# eeZeeISP.net
KiCad netlist of a schematic drawn in EAGLE
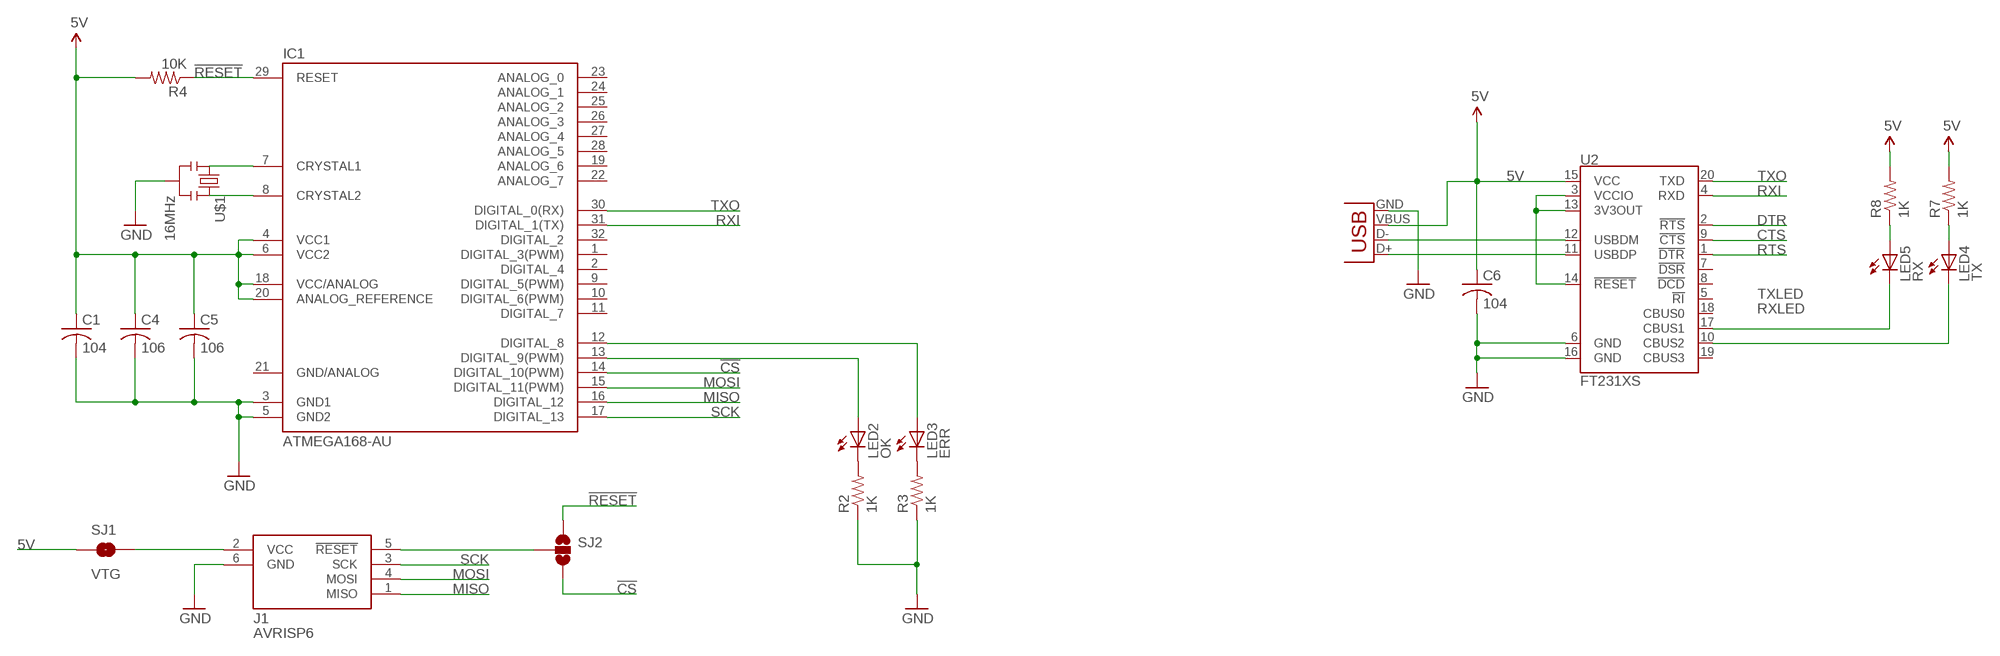
[diagram p0: schematic, sheet 1]

(export (version "E")
  (design (tool "Eeschema 10.0.6"))
  (components
    (comp (ref "C1")
      (value "104")
      (footprint "eagle-import:C0603")
      (libsource (lib "eagle-import") (part "C-USC0603"))
    )
    (comp (ref "C4")
      (value "106")
      (footprint "eagle-import:C0603")
      (libsource (lib "eagle-import") (part "C-USC0603"))
    )
    (comp (ref "C5")
      (value "106")
      (footprint "eagle-import:C0603")
      (libsource (lib "eagle-import") (part "C-USC0603"))
    )
    (comp (ref "C6")
      (value "104")
      (footprint "eagle-import:C0603")
      (libsource (lib "eagle-import") (part "C-USC0603"))
    )
    (comp (ref "IC1")
      (value "ATMEGA168-AU")
      (footprint "eagle-import:TQFP32-08")
      (libsource (lib "eagle-import") (part "ATMEGA168-AU"))
    )
    (comp (ref "J1")
      (value "AVRISP6")
      (footprint "eagle-import:CON6P2R")
      (libsource (lib "eagle-import") (part "AVRISP6"))
    )
    (comp (ref "LED2")
      (value "OK")
      (footprint "eagle-import:CHIPLED_1206")
      (libsource (lib "eagle-import") (part "LEDCHIPLED_1206"))
    )
    (comp (ref "LED3")
      (value "ERR")
      (footprint "eagle-import:CHIPLED_1206")
      (libsource (lib "eagle-import") (part "LEDCHIPLED_1206"))
    )
    (comp (ref "LED4")
      (value "TX")
      (footprint "eagle-import:CHIPLED_1206")
      (libsource (lib "eagle-import") (part "LEDCHIPLED_1206"))
    )
    (comp (ref "LED5")
      (value "RX")
      (footprint "eagle-import:CHIPLED_1206")
      (libsource (lib "eagle-import") (part "LEDCHIPLED_1206"))
    )
    (comp (ref "R2")
      (value "1K")
      (footprint "eagle-import:R0603")
      (libsource (lib "eagle-import") (part "R-US_R0603"))
    )
    (comp (ref "R3")
      (value "1K")
      (footprint "eagle-import:R0603")
      (libsource (lib "eagle-import") (part "R-US_R0603"))
    )
    (comp (ref "R4")
      (value "10K")
      (footprint "eagle-import:R0603")
      (libsource (lib "eagle-import") (part "R-US_R0603"))
    )
    (comp (ref "R7")
      (value "1K")
      (footprint "eagle-import:R0603")
      (libsource (lib "eagle-import") (part "R-US_R0603"))
    )
    (comp (ref "R8")
      (value "1K")
      (footprint "eagle-import:R0603")
      (libsource (lib "eagle-import") (part "R-US_R0603"))
    )
    (comp (ref "SJ1")
      (value "VTG")
      (footprint "eagle-import:SJ_2S-NO")
      (libsource (lib "eagle-import") (part "SOLDERJUMPERNO"))
    )
    (comp (ref "SJ2")
      (value "SOLDERJUMPER_2WAYS")
      (footprint "eagle-import:SJ_3")
      (libsource (lib "eagle-import") (part "SOLDERJUMPER_2WAYS"))
    )
    (comp (ref "U$1")
      (value "16MHz")
      (footprint "eagle-import:CSTCE_V_C")
      (libsource (lib "eagle-import") (part "RESONATOR_CSTCE_V_C"))
    )
    (comp (ref "U2")
      (value "FT231XS")
      (footprint "eagle-import:SSOP20_L")
      (libsource (lib "eagle-import") (part "FT231XS"))
    )
    (comp (ref "X2")
      (value "USB-SMD-NS")
      (footprint "eagle-import:USB-MINIB-NOSTOP")
      (libsource (lib "eagle-import") (part "USB-SMD-NS"))
    )
  )
  (nets
    (net (code "1") (name "/CTS") (class "Default")
      (node (ref "U2") (pin "9") (pinfunction "~{CTS}_9") (pintype "bidirectional"))
    )
    (net (code "2") (name "/DTR") (class "Default")
      (node (ref "U2") (pin "1") (pinfunction "~{DTR}_1") (pintype "bidirectional"))
    )
    (net (code "3") (name "/GND{slash}ANALOG") (class "Default")
      (node (ref "IC1") (pin "21") (pinfunction "GND/ANALOG_21") (pintype "power_in"))
    )
    (net (code "4") (name "/MISO") (class "Default")
      (node (ref "IC1") (pin "16") (pinfunction "DIGITAL_12_16") (pintype "bidirectional"))
      (node (ref "J1") (pin "1") (pinfunction "MISO_1") (pintype "input"))
    )
    (net (code "5") (name "/MOSI") (class "Default")
      (node (ref "IC1") (pin "15") (pinfunction "DIGITAL_11(PWM)_15") (pintype "bidirectional"))
      (node (ref "J1") (pin "4") (pinfunction "MOSI_4") (pintype "output"))
    )
    (net (code "6") (name "/RTS") (class "Default")
      (node (ref "U2") (pin "2") (pinfunction "~{RTS}_2") (pintype "bidirectional"))
    )
    (net (code "7") (name "/RXI") (class "Default")
      (node (ref "IC1") (pin "31") (pinfunction "DIGITAL_1(TX)_31") (pintype "bidirectional"))
      (node (ref "U2") (pin "4") (pinfunction "RXD_4") (pintype "bidirectional"))
    )
    (net (code "8") (name "/RXLED") (class "Default")
      (node (ref "LED5") (pin "C") (pinfunction "C_C") (pintype "passive"))
      (node (ref "U2") (pin "17") (pinfunction "CBUS1_17") (pintype "bidirectional"))
    )
    (net (code "9") (name "/SCK") (class "Default")
      (node (ref "IC1") (pin "17") (pinfunction "DIGITAL_13_17") (pintype "bidirectional"))
      (node (ref "J1") (pin "3") (pinfunction "SCK_3") (pintype "output"))
    )
    (net (code "10") (name "/TXLED") (class "Default")
      (node (ref "LED4") (pin "C") (pinfunction "C_C") (pintype "passive"))
      (node (ref "U2") (pin "10") (pinfunction "CBUS2_10") (pintype "bidirectional"))
    )
    (net (code "11") (name "/TXO") (class "Default")
      (node (ref "IC1") (pin "30") (pinfunction "DIGITAL_0(RX)_30") (pintype "bidirectional"))
      (node (ref "U2") (pin "20") (pinfunction "TXD_20") (pintype "bidirectional"))
    )
    (net (code "12") (name "/~{CS}") (class "Default")
      (node (ref "IC1") (pin "14") (pinfunction "DIGITAL_10(PWM)_14") (pintype "bidirectional"))
      (node (ref "SJ2") (pin "3") (pinfunction "3_3") (pintype "passive"))
    )
    (net (code "13") (name "/~{RESET}") (class "Default")
      (node (ref "IC1") (pin "29") (pinfunction "RESET_29") (pintype "bidirectional"))
      (node (ref "R4") (pin "1") (pinfunction "1_1") (pintype "passive"))
      (node (ref "SJ2") (pin "1") (pinfunction "1_1") (pintype "passive"))
    )
    (net (code "14") (name "5V") (class "Default")
      (node (ref "C1") (pin "1") (pinfunction "1_1") (pintype "passive"))
      (node (ref "C4") (pin "1") (pinfunction "1_1") (pintype "passive"))
      (node (ref "C5") (pin "1") (pinfunction "1_1") (pintype "passive"))
      (node (ref "C6") (pin "1") (pinfunction "1_1") (pintype "passive"))
      (node (ref "IC1") (pin "18") (pinfunction "VCC/ANALOG_18") (pintype "passive"))
      (node (ref "IC1") (pin "20") (pinfunction "ANALOG_REFERENCE_20") (pintype "passive"))
      (node (ref "IC1") (pin "4") (pinfunction "VCC1_4") (pintype "power_in"))
      (node (ref "IC1") (pin "6") (pinfunction "VCC2_6") (pintype "power_in"))
      (node (ref "R4") (pin "2") (pinfunction "2_2") (pintype "passive"))
      (node (ref "R7") (pin "2") (pinfunction "2_2") (pintype "passive"))
      (node (ref "R8") (pin "2") (pinfunction "2_2") (pintype "passive"))
      (node (ref "SJ1") (pin "1") (pinfunction "1_1") (pintype "passive"))
      (node (ref "U2") (pin "15") (pinfunction "VCC_15") (pintype "bidirectional"))
      (node (ref "X2") (pin "VBUS") (pinfunction "VBUS_VBUS") (pintype "bidirectional"))
    )
    (net (code "15") (name "GND") (class "Default")
      (node (ref "C1") (pin "2") (pinfunction "2_2") (pintype "passive"))
      (node (ref "C4") (pin "2") (pinfunction "2_2") (pintype "passive"))
      (node (ref "C5") (pin "2") (pinfunction "2_2") (pintype "passive"))
      (node (ref "C6") (pin "2") (pinfunction "2_2") (pintype "passive"))
      (node (ref "IC1") (pin "3") (pinfunction "GND1_3") (pintype "power_in"))
      (node (ref "IC1") (pin "5") (pinfunction "GND2_5") (pintype "power_in"))
      (node (ref "J1") (pin "6") (pinfunction "GND_6") (pintype "power_in"))
      (node (ref "R2") (pin "1") (pinfunction "1_1") (pintype "passive"))
      (node (ref "R3") (pin "1") (pinfunction "1_1") (pintype "passive"))
      (node (ref "U$1") (pin "GND") (pinfunction "GND_GND") (pintype "passive"))
      (node (ref "U2") (pin "16") (pinfunction "GND_16") (pintype "bidirectional"))
      (node (ref "U2") (pin "6") (pinfunction "GND_6") (pintype "bidirectional"))
      (node (ref "X2") (pin "GND") (pinfunction "GND_GND") (pintype "bidirectional"))
    )
    (net (code "16") (name "Net-(IC1-CRYSTAL1)") (class "Default")
      (node (ref "IC1") (pin "7") (pinfunction "CRYSTAL1_7") (pintype "bidirectional"))
      (node (ref "U$1") (pin "X1") (pinfunction "X1_X1") (pintype "passive"))
    )
    (net (code "17") (name "Net-(IC1-CRYSTAL2)") (class "Default")
      (node (ref "IC1") (pin "8") (pinfunction "CRYSTAL2_8") (pintype "bidirectional"))
      (node (ref "U$1") (pin "X2") (pinfunction "X2_X2") (pintype "passive"))
    )
    (net (code "18") (name "Net-(IC1-DIGITAL_8)") (class "Default")
      (node (ref "IC1") (pin "12") (pinfunction "DIGITAL_8_12") (pintype "bidirectional"))
      (node (ref "LED3") (pin "A") (pinfunction "A_A") (pintype "passive"))
    )
    (net (code "19") (name "Net-(IC1-DIGITAL_9(PWM))") (class "Default")
      (node (ref "IC1") (pin "13") (pinfunction "DIGITAL_9(PWM)_13") (pintype "bidirectional"))
      (node (ref "LED2") (pin "A") (pinfunction "A_A") (pintype "passive"))
    )
    (net (code "20") (name "Net-(J1-VCC)") (class "Default")
      (node (ref "J1") (pin "2") (pinfunction "VCC_2") (pintype "power_in"))
      (node (ref "SJ1") (pin "2") (pinfunction "2_2") (pintype "passive"))
    )
    (net (code "21") (name "Net-(J1-~{RESET})") (class "Default")
      (node (ref "J1") (pin "5") (pinfunction "~{RESET}_5") (pintype "output"))
      (node (ref "SJ2") (pin "2") (pinfunction "2_2") (pintype "passive"))
    )
    (net (code "22") (name "Net-(LED2-PadC)") (class "Default")
      (node (ref "LED2") (pin "C") (pinfunction "C_C") (pintype "passive"))
      (node (ref "R2") (pin "2") (pinfunction "2_2") (pintype "passive"))
    )
    (net (code "23") (name "Net-(LED3-PadC)") (class "Default")
      (node (ref "LED3") (pin "C") (pinfunction "C_C") (pintype "passive"))
      (node (ref "R3") (pin "2") (pinfunction "2_2") (pintype "passive"))
    )
    (net (code "24") (name "Net-(LED4-PadA)") (class "Default")
      (node (ref "LED4") (pin "A") (pinfunction "A_A") (pintype "passive"))
      (node (ref "R7") (pin "1") (pinfunction "1_1") (pintype "passive"))
    )
    (net (code "25") (name "Net-(LED5-PadA)") (class "Default")
      (node (ref "LED5") (pin "A") (pinfunction "A_A") (pintype "passive"))
      (node (ref "R8") (pin "1") (pinfunction "1_1") (pintype "passive"))
    )
    (net (code "26") (name "Net-(U2-3V3OUT)") (class "Default")
      (node (ref "U2") (pin "13") (pinfunction "3V3OUT_13") (pintype "bidirectional"))
      (node (ref "U2") (pin "14") (pinfunction "~{RESET}_14") (pintype "bidirectional"))
      (node (ref "U2") (pin "3") (pinfunction "VCCIO_3") (pintype "bidirectional"))
    )
    (net (code "27") (name "Net-(U2-USBDM)") (class "Default")
      (node (ref "U2") (pin "12") (pinfunction "USBDM_12") (pintype "bidirectional"))
      (node (ref "X2") (pin "D-") (pinfunction "D-_D-") (pintype "bidirectional"))
    )
    (net (code "28") (name "Net-(U2-USBDP)") (class "Default")
      (node (ref "U2") (pin "11") (pinfunction "USBDP_11") (pintype "bidirectional"))
      (node (ref "X2") (pin "D+") (pinfunction "D+_D+") (pintype "bidirectional"))
    )
    (net (code "29") (name "unconnected-(IC1-ANALOG_0-Pad23)") (class "Default")
      (node (ref "IC1") (pin "23") (pinfunction "ANALOG_0_23") (pintype "bidirectional"))
    )
    (net (code "30") (name "unconnected-(IC1-ANALOG_1-Pad24)") (class "Default")
      (node (ref "IC1") (pin "24") (pinfunction "ANALOG_1_24") (pintype "bidirectional"))
    )
    (net (code "31") (name "unconnected-(IC1-ANALOG_2-Pad25)") (class "Default")
      (node (ref "IC1") (pin "25") (pinfunction "ANALOG_2_25") (pintype "bidirectional"))
    )
    (net (code "32") (name "unconnected-(IC1-ANALOG_3-Pad26)") (class "Default")
      (node (ref "IC1") (pin "26") (pinfunction "ANALOG_3_26") (pintype "bidirectional"))
    )
    (net (code "33") (name "unconnected-(IC1-ANALOG_4-Pad27)") (class "Default")
      (node (ref "IC1") (pin "27") (pinfunction "ANALOG_4_27") (pintype "bidirectional"))
    )
    (net (code "34") (name "unconnected-(IC1-ANALOG_5-Pad28)") (class "Default")
      (node (ref "IC1") (pin "28") (pinfunction "ANALOG_5_28") (pintype "bidirectional"))
    )
    (net (code "35") (name "unconnected-(IC1-ANALOG_6-Pad19)") (class "Default")
      (node (ref "IC1") (pin "19") (pinfunction "ANALOG_6_19") (pintype "passive"))
    )
    (net (code "36") (name "unconnected-(IC1-ANALOG_7-Pad22)") (class "Default")
      (node (ref "IC1") (pin "22") (pinfunction "ANALOG_7_22") (pintype "passive"))
    )
    (net (code "37") (name "unconnected-(IC1-DIGITAL_2-Pad32)") (class "Default")
      (node (ref "IC1") (pin "32") (pinfunction "DIGITAL_2_32") (pintype "bidirectional"))
    )
    (net (code "38") (name "unconnected-(IC1-DIGITAL_3(PWM)-Pad1)") (class "Default")
      (node (ref "IC1") (pin "1") (pinfunction "DIGITAL_3(PWM)_1") (pintype "bidirectional"))
    )
    (net (code "39") (name "unconnected-(IC1-DIGITAL_4-Pad2)") (class "Default")
      (node (ref "IC1") (pin "2") (pinfunction "DIGITAL_4_2") (pintype "bidirectional"))
    )
    (net (code "40") (name "unconnected-(IC1-DIGITAL_5(PWM)-Pad9)") (class "Default")
      (node (ref "IC1") (pin "9") (pinfunction "DIGITAL_5(PWM)_9") (pintype "bidirectional"))
    )
    (net (code "41") (name "unconnected-(IC1-DIGITAL_6(PWM)-Pad10)") (class "Default")
      (node (ref "IC1") (pin "10") (pinfunction "DIGITAL_6(PWM)_10") (pintype "bidirectional"))
    )
    (net (code "42") (name "unconnected-(IC1-DIGITAL_7-Pad11)") (class "Default")
      (node (ref "IC1") (pin "11") (pinfunction "DIGITAL_7_11") (pintype "bidirectional"))
    )
    (net (code "43") (name "unconnected-(U2-CBUS0-Pad18)") (class "Default")
      (node (ref "U2") (pin "18") (pinfunction "CBUS0_18") (pintype "bidirectional"))
    )
    (net (code "44") (name "unconnected-(U2-CBUS3-Pad19)") (class "Default")
      (node (ref "U2") (pin "19") (pinfunction "CBUS3_19") (pintype "bidirectional"))
    )
    (net (code "45") (name "unconnected-(U2-~{DCD}-Pad8)") (class "Default")
      (node (ref "U2") (pin "8") (pinfunction "~{DCD}_8") (pintype "bidirectional"))
    )
    (net (code "46") (name "unconnected-(U2-~{DSR}-Pad7)") (class "Default")
      (node (ref "U2") (pin "7") (pinfunction "~{DSR}_7") (pintype "bidirectional"))
    )
    (net (code "47") (name "unconnected-(U2-~{RI}-Pad5)") (class "Default")
      (node (ref "U2") (pin "5") (pinfunction "~{RI}_5") (pintype "bidirectional"))
    )
  )
)
